# Mtx6BR_V2.net
KiCad netlist of a schematic drawn in EAGLE
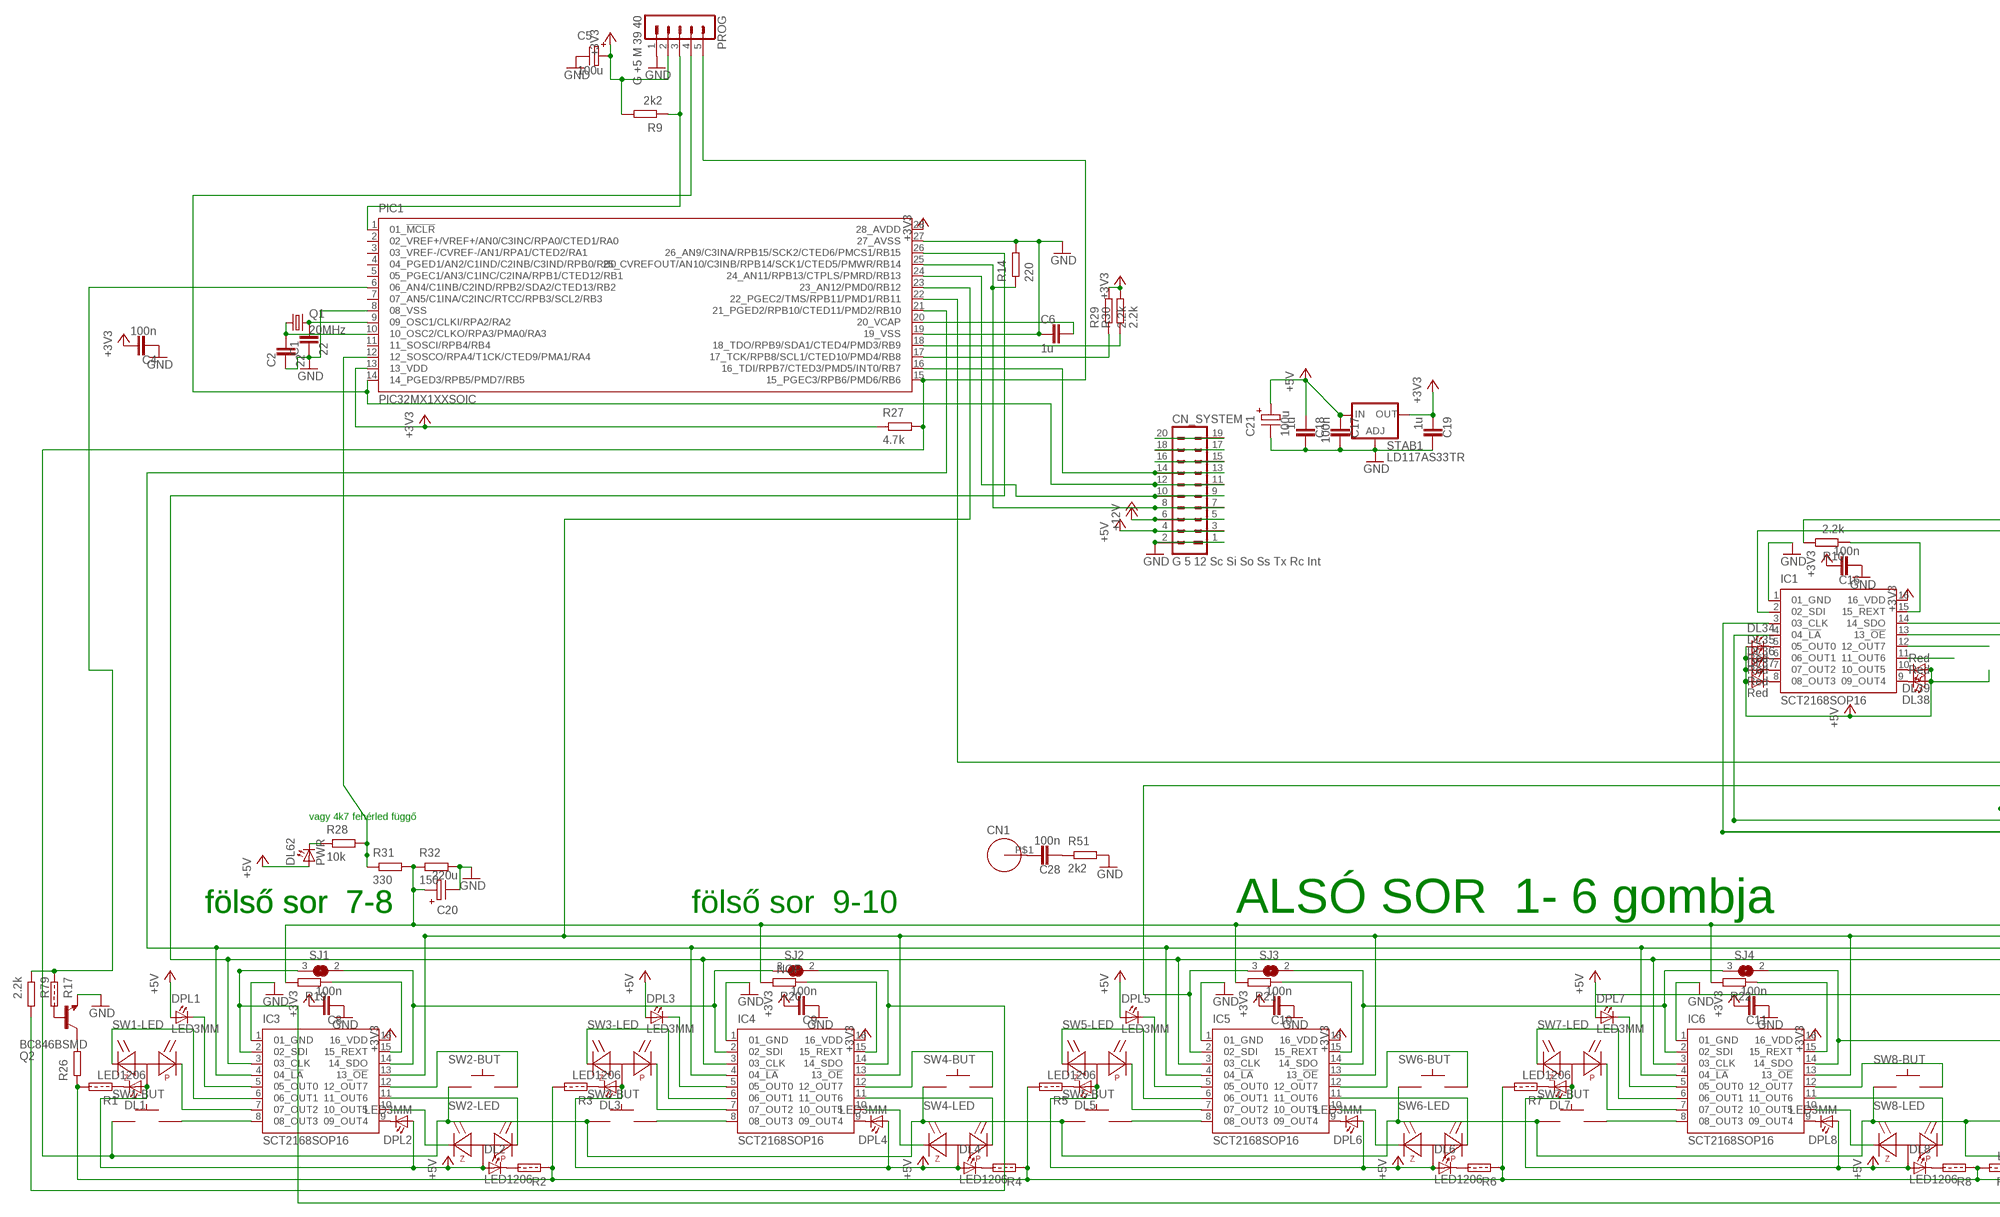
[diagram p0: schematic, sheet 1, part 1 of 2]
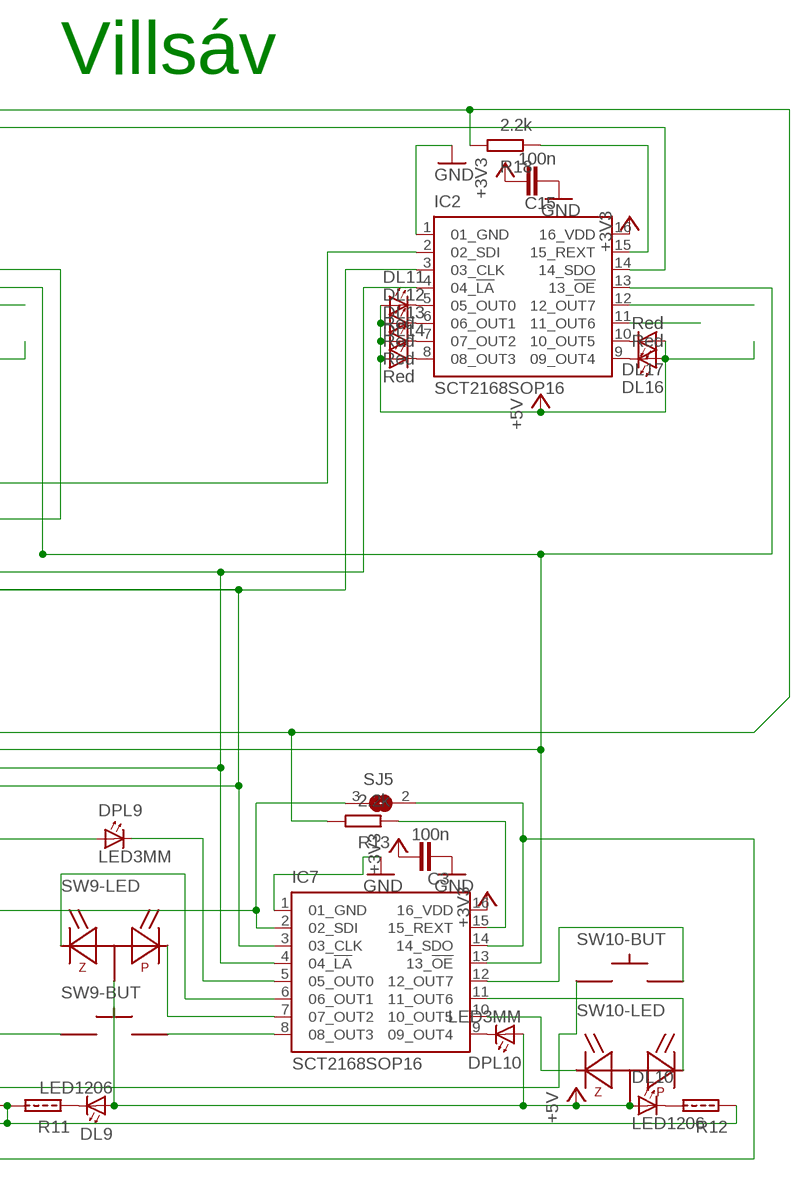
[diagram p1: schematic, sheet 1, part 2 of 2]

(export (version "E")
  (design (tool "Eeschema 10.0.6"))
  (components
    (comp (ref "C1")
      (value "22")
      (footprint "eagle-import:R0805")
      (libsource (lib "eagle-import") (part "C0805"))
    )
    (comp (ref "C2")
      (value "22")
      (footprint "eagle-import:R0805")
      (libsource (lib "eagle-import") (part "C0805"))
    )
    (comp (ref "C3")
      (value "100n")
      (footprint "eagle-import:R0805")
      (libsource (lib "eagle-import") (part "C0805"))
    )
    (comp (ref "C4")
      (value "100n")
      (footprint "eagle-import:R0805")
      (libsource (lib "eagle-import") (part "C0805"))
    )
    (comp (ref "C5")
      (value "100u")
      (footprint "eagle-import:C_EL1RASZT07")
      (libsource (lib "eagle-import") (part "C_EL1R07"))
    )
    (comp (ref "C6")
      (value "1u")
      (footprint "eagle-import:R0805")
      (libsource (lib "eagle-import") (part "C0805"))
    )
    (comp (ref "C8")
      (value "100n")
      (footprint "eagle-import:R0805")
      (libsource (lib "eagle-import") (part "C0805"))
    )
    (comp (ref "C9")
      (value "100n")
      (footprint "eagle-import:R0805")
      (libsource (lib "eagle-import") (part "C0805"))
    )
    (comp (ref "C10")
      (value "100n")
      (footprint "eagle-import:R0805")
      (libsource (lib "eagle-import") (part "C0805"))
    )
    (comp (ref "C11")
      (value "100n")
      (footprint "eagle-import:R0805")
      (libsource (lib "eagle-import") (part "C0805"))
    )
    (comp (ref "C15")
      (value "100n")
      (footprint "eagle-import:R0805")
      (libsource (lib "eagle-import") (part "C0805"))
    )
    (comp (ref "C16")
      (value "100n")
      (footprint "eagle-import:R0805")
      (libsource (lib "eagle-import") (part "C0805"))
    )
    (comp (ref "C17")
      (value "100n")
      (footprint "eagle-import:R0805")
      (libsource (lib "eagle-import") (part "C0805"))
    )
    (comp (ref "C18")
      (value "1u")
      (footprint "eagle-import:R0805")
      (libsource (lib "eagle-import") (part "C0805"))
    )
    (comp (ref "C19")
      (value "1u")
      (footprint "eagle-import:R0805")
      (libsource (lib "eagle-import") (part "C0805"))
    )
    (comp (ref "C20")
      (value "220u")
      (footprint "eagle-import:C_EL1RASZT07")
      (libsource (lib "eagle-import") (part "C_EL1R07"))
    )
    (comp (ref "C21")
      (value "100u")
      (footprint "eagle-import:C_EL1RASZT07")
      (libsource (lib "eagle-import") (part "C_EL1R07"))
    )
    (comp (ref "C28")
      (value "100n")
      (footprint "eagle-import:R0805")
      (libsource (lib "eagle-import") (part "C0805"))
    )
    (comp (ref "CN1")
      (value "TESTCSAVAR3.5")
      (footprint "eagle-import:TESTCSAVAR_3.5")
      (libsource (lib "eagle-import") (part "TESTCSAVAR3.5"))
    )
    (comp (ref "CN_SYSTEM")
      (value "G 5 12 Sc Si So Ss Tx Rc Int")
      (footprint "eagle-import:PIN10_2")
      (libsource (lib "eagle-import") (part "PIN10_2"))
    )
    (comp (ref "DL1")
      (value "LED1206")
      (footprint "eagle-import:R1206")
      (libsource (lib "eagle-import") (part "LED1206"))
    )
    (comp (ref "DL2")
      (value "LED1206")
      (footprint "eagle-import:R1206")
      (libsource (lib "eagle-import") (part "LED1206"))
    )
    (comp (ref "DL3")
      (value "LED1206")
      (footprint "eagle-import:R1206")
      (libsource (lib "eagle-import") (part "LED1206"))
    )
    (comp (ref "DL4")
      (value "LED1206")
      (footprint "eagle-import:R1206")
      (libsource (lib "eagle-import") (part "LED1206"))
    )
    (comp (ref "DL5")
      (value "LED1206")
      (footprint "eagle-import:R1206")
      (libsource (lib "eagle-import") (part "LED1206"))
    )
    (comp (ref "DL6")
      (value "LED1206")
      (footprint "eagle-import:R1206")
      (libsource (lib "eagle-import") (part "LED1206"))
    )
    (comp (ref "DL7")
      (value "LED1206")
      (footprint "eagle-import:R1206")
      (libsource (lib "eagle-import") (part "LED1206"))
    )
    (comp (ref "DL8")
      (value "LED1206")
      (footprint "eagle-import:R1206")
      (libsource (lib "eagle-import") (part "LED1206"))
    )
    (comp (ref "DL9")
      (value "LED1206")
      (footprint "eagle-import:R1206")
      (libsource (lib "eagle-import") (part "LED1206"))
    )
    (comp (ref "DL10")
      (value "LED1206")
      (footprint "eagle-import:R1206")
      (libsource (lib "eagle-import") (part "LED1206"))
    )
    (comp (ref "DL11")
      (value "Red")
      (footprint "eagle-import:LED5MM")
      (libsource (lib "eagle-import") (part "LED5MM"))
    )
    (comp (ref "DL12")
      (value "Red")
      (footprint "eagle-import:LED5MM")
      (libsource (lib "eagle-import") (part "LED5MM"))
    )
    (comp (ref "DL13")
      (value "Red")
      (footprint "eagle-import:LED5MM")
      (libsource (lib "eagle-import") (part "LED5MM"))
    )
    (comp (ref "DL14")
      (value "Red")
      (footprint "eagle-import:LED5MM")
      (libsource (lib "eagle-import") (part "LED5MM"))
    )
    (comp (ref "DL16")
      (value "Red")
      (footprint "eagle-import:LED5MM")
      (libsource (lib "eagle-import") (part "LED5MM"))
    )
    (comp (ref "DL17")
      (value "Red")
      (footprint "eagle-import:LED5MM")
      (libsource (lib "eagle-import") (part "LED5MM"))
    )
    (comp (ref "DL34")
      (value "Red")
      (footprint "eagle-import:LED5MM")
      (libsource (lib "eagle-import") (part "LED5MM"))
    )
    (comp (ref "DL35")
      (value "Red")
      (footprint "eagle-import:LED5MM")
      (libsource (lib "eagle-import") (part "LED5MM"))
    )
    (comp (ref "DL36")
      (value "Red")
      (footprint "eagle-import:LED5MM")
      (libsource (lib "eagle-import") (part "LED5MM"))
    )
    (comp (ref "DL37")
      (value "Red")
      (footprint "eagle-import:LED5MM")
      (libsource (lib "eagle-import") (part "LED5MM"))
    )
    (comp (ref "DL38")
      (value "Red")
      (footprint "eagle-import:LED5MM")
      (libsource (lib "eagle-import") (part "LED5MM"))
    )
    (comp (ref "DL39")
      (value "Red")
      (footprint "eagle-import:LED5MM")
      (libsource (lib "eagle-import") (part "LED5MM"))
    )
    (comp (ref "DL62")
      (value "PWR")
      (footprint "eagle-import:LED5MM")
      (libsource (lib "eagle-import") (part "LED5MM"))
    )
    (comp (ref "DPL1")
      (value "LED3MM")
      (footprint "eagle-import:LED3MM")
      (libsource (lib "eagle-import") (part "LED3MM"))
    )
    (comp (ref "DPL2")
      (value "LED3MM")
      (footprint "eagle-import:LED3MM")
      (libsource (lib "eagle-import") (part "LED3MM"))
    )
    (comp (ref "DPL3")
      (value "LED3MM")
      (footprint "eagle-import:LED3MM")
      (libsource (lib "eagle-import") (part "LED3MM"))
    )
    (comp (ref "DPL4")
      (value "LED3MM")
      (footprint "eagle-import:LED3MM")
      (libsource (lib "eagle-import") (part "LED3MM"))
    )
    (comp (ref "DPL5")
      (value "LED3MM")
      (footprint "eagle-import:LED3MM")
      (libsource (lib "eagle-import") (part "LED3MM"))
    )
    (comp (ref "DPL6")
      (value "LED3MM")
      (footprint "eagle-import:LED3MM")
      (libsource (lib "eagle-import") (part "LED3MM"))
    )
    (comp (ref "DPL7")
      (value "LED3MM")
      (footprint "eagle-import:LED3MM")
      (libsource (lib "eagle-import") (part "LED3MM"))
    )
    (comp (ref "DPL8")
      (value "LED3MM")
      (footprint "eagle-import:LED3MM")
      (libsource (lib "eagle-import") (part "LED3MM"))
    )
    (comp (ref "DPL9")
      (value "LED3MM")
      (footprint "eagle-import:LED3MM")
      (libsource (lib "eagle-import") (part "LED3MM"))
    )
    (comp (ref "DPL10")
      (value "LED3MM")
      (footprint "eagle-import:LED3MM")
      (libsource (lib "eagle-import") (part "LED3MM"))
    )
    (comp (ref "IC1")
      (value "SCT2168SOP16")
      (footprint "eagle-import:SO16")
      (libsource (lib "eagle-import") (part "SCT2168SOP16"))
    )
    (comp (ref "IC2")
      (value "SCT2168SOP16")
      (footprint "eagle-import:SO16")
      (libsource (lib "eagle-import") (part "SCT2168SOP16"))
    )
    (comp (ref "IC3")
      (value "SCT2168SOP16")
      (footprint "eagle-import:SO16")
      (libsource (lib "eagle-import") (part "SCT2168SOP16"))
    )
    (comp (ref "IC4")
      (value "SCT2168SOP16")
      (footprint "eagle-import:SO16")
      (libsource (lib "eagle-import") (part "SCT2168SOP16"))
    )
    (comp (ref "IC5")
      (value "SCT2168SOP16")
      (footprint "eagle-import:SO16")
      (libsource (lib "eagle-import") (part "SCT2168SOP16"))
    )
    (comp (ref "IC6")
      (value "SCT2168SOP16")
      (footprint "eagle-import:SO16")
      (libsource (lib "eagle-import") (part "SCT2168SOP16"))
    )
    (comp (ref "IC7")
      (value "SCT2168SOP16")
      (footprint "eagle-import:SO16")
      (libsource (lib "eagle-import") (part "SCT2168SOP16"))
    )
    (comp (ref "PIC1")
      (value "PIC32MX1XXSOIC")
      (footprint "eagle-import:SOIC127P1032X265-28N")
      (libsource (lib "eagle-import") (part "PIC32MX1XXSOIC"))
    )
    (comp (ref "PROG")
      (value "G +5 M 39 40")
      (footprint "eagle-import:PIN05_1")
      (libsource (lib "eagle-import") (part "PIN05_1"))
    )
    (comp (ref "Q1")
      (value "20MHz")
      (footprint "eagle-import:XTAL_NAGYSMD")
      (libsource (lib "eagle-import") (part "XTAL_2NAGYSMD"))
    )
    (comp (ref "Q2")
      (value "BC846BSMD")
      (footprint "eagle-import:SOT23")
      (libsource (lib "eagle-import") (part "BC846SMDB"))
    )
    (comp (ref "R1")
      (value "RNULL_EU0805")
      (footprint "eagle-import:R0805_C")
      (libsource (lib "eagle-import") (part "RNULL_EU0805"))
    )
    (comp (ref "R2")
      (value "RNULL_EU0805")
      (footprint "eagle-import:R0805_C")
      (libsource (lib "eagle-import") (part "RNULL_EU0805"))
    )
    (comp (ref "R3")
      (value "RNULL_EU0805")
      (footprint "eagle-import:R0805_C")
      (libsource (lib "eagle-import") (part "RNULL_EU0805"))
    )
    (comp (ref "R4")
      (value "RNULL_EU0805")
      (footprint "eagle-import:R0805_C")
      (libsource (lib "eagle-import") (part "RNULL_EU0805"))
    )
    (comp (ref "R5")
      (value "RNULL_EU0805")
      (footprint "eagle-import:R0805_C")
      (libsource (lib "eagle-import") (part "RNULL_EU0805"))
    )
    (comp (ref "R6")
      (value "RNULL_EU0805")
      (footprint "eagle-import:R0805_C")
      (libsource (lib "eagle-import") (part "RNULL_EU0805"))
    )
    (comp (ref "R7")
      (value "RNULL_EU0805")
      (footprint "eagle-import:R0805_C")
      (libsource (lib "eagle-import") (part "RNULL_EU0805"))
    )
    (comp (ref "R8")
      (value "RNULL_EU0805")
      (footprint "eagle-import:R0805_C")
      (libsource (lib "eagle-import") (part "RNULL_EU0805"))
    )
    (comp (ref "R9")
      (value "2k2")
      (footprint "eagle-import:R0805")
      (libsource (lib "eagle-import") (part "R_EU0805"))
    )
    (comp (ref "R10")
      (value "2.2k")
      (footprint "eagle-import:R0805")
      (libsource (lib "eagle-import") (part "R_EU0805"))
    )
    (comp (ref "R11")
      (value "RNULL_EU0805")
      (footprint "eagle-import:R0805_C")
      (libsource (lib "eagle-import") (part "RNULL_EU0805"))
    )
    (comp (ref "R12")
      (value "RNULL_EU0805")
      (footprint "eagle-import:R0805_C")
      (libsource (lib "eagle-import") (part "RNULL_EU0805"))
    )
    (comp (ref "R13")
      (value "2.2k")
      (footprint "eagle-import:R0805")
      (libsource (lib "eagle-import") (part "R_EU0805"))
    )
    (comp (ref "R14")
      (value "220")
      (footprint "eagle-import:R0805")
      (libsource (lib "eagle-import") (part "R_EU0805"))
    )
    (comp (ref "R17")
      (value "RNULL_EU0805")
      (footprint "eagle-import:R0805_C")
      (libsource (lib "eagle-import") (part "RNULL_EU0805"))
    )
    (comp (ref "R18")
      (value "2.2k")
      (footprint "eagle-import:R0805")
      (libsource (lib "eagle-import") (part "R_EU0805"))
    )
    (comp (ref "R19")
      (value "R_EU0805")
      (footprint "eagle-import:R0805")
      (libsource (lib "eagle-import") (part "R_EU0805"))
    )
    (comp (ref "R20")
      (value "NOP")
      (footprint "eagle-import:R0805")
      (libsource (lib "eagle-import") (part "R_EU0805"))
    )
    (comp (ref "R21")
      (value "R_EU0805")
      (footprint "eagle-import:R0805")
      (libsource (lib "eagle-import") (part "R_EU0805"))
    )
    (comp (ref "R22")
      (value "R_EU0805")
      (footprint "eagle-import:R0805")
      (libsource (lib "eagle-import") (part "R_EU0805"))
    )
    (comp (ref "R26")
      (value "R_EU0805")
      (footprint "eagle-import:R0805")
      (libsource (lib "eagle-import") (part "R_EU0805"))
    )
    (comp (ref "R27")
      (value "4.7k")
      (footprint "eagle-import:R0805")
      (libsource (lib "eagle-import") (part "R_EU0805"))
    )
    (comp (ref "R28")
      (value "10k")
      (footprint "eagle-import:R0805")
      (libsource (lib "eagle-import") (part "R_EU0805"))
    )
    (comp (ref "R29")
      (value "2.2k")
      (footprint "eagle-import:R0805")
      (libsource (lib "eagle-import") (part "R_EU0805"))
    )
    (comp (ref "R30")
      (value "2.2k")
      (footprint "eagle-import:R0805")
      (libsource (lib "eagle-import") (part "R_EU0805"))
    )
    (comp (ref "R31")
      (value "330")
      (footprint "eagle-import:R0805")
      (libsource (lib "eagle-import") (part "R_EU0805"))
    )
    (comp (ref "R32")
      (value "150")
      (footprint "eagle-import:R0805")
      (libsource (lib "eagle-import") (part "R_EU0805"))
    )
    (comp (ref "R51")
      (value "2k2")
      (footprint "eagle-import:R0805")
      (libsource (lib "eagle-import") (part "R_EU0805"))
    )
    (comp (ref "R79")
      (value "2.2k")
      (footprint "eagle-import:R0805")
      (libsource (lib "eagle-import") (part "R_EU0805"))
    )
    (comp (ref "SJ1") (value "SJ") (footprint "eagle-import:SJ") (libsource (lib "eagle-import") (part "SJ")))
    (comp (ref "SJ2") (value "SJ") (footprint "eagle-import:SJ") (libsource (lib "eagle-import") (part "SJ")))
    (comp (ref "SJ3") (value "SJ") (footprint "eagle-import:SJ") (libsource (lib "eagle-import") (part "SJ")))
    (comp (ref "SJ4") (value "SJ") (footprint "eagle-import:SJ") (libsource (lib "eagle-import") (part "SJ")))
    (comp (ref "SJ5") (value "SJ") (footprint "eagle-import:SJ") (libsource (lib "eagle-import") (part "SJ")))
    (comp (ref "STAB1")
      (value "LD117AS33TR")
      (footprint "eagle-import:SOT223")
      (libsource (lib "eagle-import") (part "LD117A?S33TR"))
    )
    (comp (ref "SW1")
      (value "SPG2")
      (footprint "eagle-import:SPG2_3LED")
      (libsource (lib "eagle-import") (part "SPG2"))
    )
    (comp (ref "SW2")
      (value "SPG2")
      (footprint "eagle-import:SPG2_3LED")
      (libsource (lib "eagle-import") (part "SPG2"))
    )
    (comp (ref "SW3")
      (value "SPG2")
      (footprint "eagle-import:SPG2_3LED")
      (libsource (lib "eagle-import") (part "SPG2"))
    )
    (comp (ref "SW4")
      (value "SPG2")
      (footprint "eagle-import:SPG2_3LED")
      (libsource (lib "eagle-import") (part "SPG2"))
    )
    (comp (ref "SW5")
      (value "SPG2")
      (footprint "eagle-import:SPG2_3LED")
      (libsource (lib "eagle-import") (part "SPG2"))
    )
    (comp (ref "SW6")
      (value "SPG2")
      (footprint "eagle-import:SPG2_3LED")
      (libsource (lib "eagle-import") (part "SPG2"))
    )
    (comp (ref "SW7")
      (value "SPG2")
      (footprint "eagle-import:SPG2_3LED")
      (libsource (lib "eagle-import") (part "SPG2"))
    )
    (comp (ref "SW8")
      (value "SPG2")
      (footprint "eagle-import:SPG2_3LED")
      (libsource (lib "eagle-import") (part "SPG2"))
    )
    (comp (ref "SW9")
      (value "SPG2")
      (footprint "eagle-import:SPG2_3LED")
      (libsource (lib "eagle-import") (part "SPG2"))
    )
    (comp (ref "SW10")
      (value "SPG2")
      (footprint "eagle-import:SPG2_3LED")
      (libsource (lib "eagle-import") (part "SPG2"))
    )
  )
  (nets
    (net (code "1") (name "+3V3") (class "Default")
      (node (ref "C10") (pin "1") (pinfunction "1_1") (pintype "passive"))
      (node (ref "C11") (pin "1") (pinfunction "1_1") (pintype "passive"))
      (node (ref "C15") (pin "1") (pinfunction "1_1") (pintype "passive"))
      (node (ref "C16") (pin "1") (pinfunction "1_1") (pintype "passive"))
      (node (ref "C19") (pin "2") (pinfunction "2_2") (pintype "passive"))
      (node (ref "C3") (pin "1") (pinfunction "1_1") (pintype "passive"))
      (node (ref "C4") (pin "1") (pinfunction "1_1") (pintype "passive"))
      (node (ref "C5") (pin "P+") (pinfunction "P+_P+") (pintype "passive"))
      (node (ref "C8") (pin "1") (pinfunction "1_1") (pintype "passive"))
      (node (ref "C9") (pin "1") (pinfunction "1_1") (pintype "passive"))
      (node (ref "IC1") (pin "16") (pinfunction "16_VDD_16") (pintype "power_in"))
      (node (ref "IC2") (pin "16") (pinfunction "16_VDD_16") (pintype "power_in"))
      (node (ref "IC3") (pin "16") (pinfunction "16_VDD_16") (pintype "power_in"))
      (node (ref "IC4") (pin "16") (pinfunction "16_VDD_16") (pintype "power_in"))
      (node (ref "IC5") (pin "16") (pinfunction "16_VDD_16") (pintype "power_in"))
      (node (ref "IC6") (pin "16") (pinfunction "16_VDD_16") (pintype "power_in"))
      (node (ref "IC7") (pin "16") (pinfunction "16_VDD_16") (pintype "power_in"))
      (node (ref "PIC1") (pin "13") (pinfunction "13_VDD_13") (pintype "bidirectional"))
      (node (ref "PIC1") (pin "28") (pinfunction "28_AVDD_28") (pintype "bidirectional"))
      (node (ref "PROG") (pin "2") (pinfunction "2_2") (pintype "passive"))
      (node (ref "R27") (pin "1") (pinfunction "A_1") (pintype "passive"))
      (node (ref "R29") (pin "2") (pinfunction "E_2") (pintype "passive"))
      (node (ref "R30") (pin "2") (pinfunction "E_2") (pintype "passive"))
      (node (ref "R9") (pin "2") (pinfunction "E_2") (pintype "passive"))
      (node (ref "STAB1") (pin "4") (pinfunction "OUT_4") (pintype "passive"))
    )
    (net (code "2") (name "+5V") (class "Default")
      (node (ref "C17") (pin "2") (pinfunction "2_2") (pintype "passive"))
      (node (ref "C18") (pin "2") (pinfunction "2_2") (pintype "passive"))
      (node (ref "C21") (pin "P+") (pinfunction "P+_P+") (pintype "passive"))
      (node (ref "CN_SYSTEM") (pin "3") (pinfunction "3_3") (pintype "passive"))
      (node (ref "CN_SYSTEM") (pin "4") (pinfunction "4_4") (pintype "passive"))
      (node (ref "DL1") (pin "1") (pinfunction "A_1") (pintype "passive"))
      (node (ref "DL10") (pin "1") (pinfunction "A_1") (pintype "passive"))
      (node (ref "DL11") (pin "A") (pinfunction "A_A") (pintype "passive"))
      (node (ref "DL12") (pin "A") (pinfunction "A_A") (pintype "passive"))
      (node (ref "DL13") (pin "A") (pinfunction "A_A") (pintype "passive"))
      (node (ref "DL14") (pin "A") (pinfunction "A_A") (pintype "passive"))
      (node (ref "DL16") (pin "A") (pinfunction "A_A") (pintype "passive"))
      (node (ref "DL17") (pin "A") (pinfunction "A_A") (pintype "passive"))
      (node (ref "DL2") (pin "1") (pinfunction "A_1") (pintype "passive"))
      (node (ref "DL3") (pin "1") (pinfunction "A_1") (pintype "passive"))
      (node (ref "DL34") (pin "A") (pinfunction "A_A") (pintype "passive"))
      (node (ref "DL35") (pin "A") (pinfunction "A_A") (pintype "passive"))
      (node (ref "DL36") (pin "A") (pinfunction "A_A") (pintype "passive"))
      (node (ref "DL37") (pin "A") (pinfunction "A_A") (pintype "passive"))
      (node (ref "DL38") (pin "A") (pinfunction "A_A") (pintype "passive"))
      (node (ref "DL39") (pin "A") (pinfunction "A_A") (pintype "passive"))
      (node (ref "DL4") (pin "1") (pinfunction "A_1") (pintype "passive"))
      (node (ref "DL5") (pin "1") (pinfunction "A_1") (pintype "passive"))
      (node (ref "DL6") (pin "1") (pinfunction "A_1") (pintype "passive"))
      (node (ref "DL62") (pin "A") (pinfunction "A_A") (pintype "passive"))
      (node (ref "DL7") (pin "1") (pinfunction "A_1") (pintype "passive"))
      (node (ref "DL8") (pin "1") (pinfunction "A_1") (pintype "passive"))
      (node (ref "DL9") (pin "1") (pinfunction "A_1") (pintype "passive"))
      (node (ref "DPL1") (pin "A") (pinfunction "A_A") (pintype "passive"))
      (node (ref "DPL10") (pin "A") (pinfunction "A_A") (pintype "passive"))
      (node (ref "DPL2") (pin "A") (pinfunction "A_A") (pintype "passive"))
      (node (ref "DPL3") (pin "A") (pinfunction "A_A") (pintype "passive"))
      (node (ref "DPL4") (pin "A") (pinfunction "A_A") (pintype "passive"))
      (node (ref "DPL5") (pin "A") (pinfunction "A_A") (pintype "passive"))
      (node (ref "DPL6") (pin "A") (pinfunction "A_A") (pintype "passive"))
      (node (ref "DPL7") (pin "A") (pinfunction "A_A") (pintype "passive"))
      (node (ref "DPL8") (pin "A") (pinfunction "A_A") (pintype "passive"))
      (node (ref "DPL9") (pin "A") (pinfunction "A_A") (pintype "passive"))
      (node (ref "STAB1") (pin "3") (pinfunction "IN_3") (pintype "input"))
      (node (ref "SW1") (pin "LED+") (pinfunction "+_LED+") (pintype "bidirectional"))
      (node (ref "SW10") (pin "LED+") (pinfunction "+_LED+") (pintype "bidirectional"))
      (node (ref "SW2") (pin "LED+") (pinfunction "+_LED+") (pintype "bidirectional"))
      (node (ref "SW3") (pin "LED+") (pinfunction "+_LED+") (pintype "bidirectional"))
      (node (ref "SW4") (pin "LED+") (pinfunction "+_LED+") (pintype "bidirectional"))
      (node (ref "SW5") (pin "LED+") (pinfunction "+_LED+") (pintype "bidirectional"))
      (node (ref "SW6") (pin "LED+") (pinfunction "+_LED+") (pintype "bidirectional"))
      (node (ref "SW7") (pin "LED+") (pinfunction "+_LED+") (pintype "bidirectional"))
      (node (ref "SW8") (pin "LED+") (pinfunction "+_LED+") (pintype "bidirectional"))
      (node (ref "SW9") (pin "LED+") (pinfunction "+_LED+") (pintype "bidirectional"))
    )
    (net (code "3") (name "+12V") (class "Default")
      (node (ref "CN_SYSTEM") (pin "5") (pinfunction "5_5") (pintype "passive"))
      (node (ref "CN_SYSTEM") (pin "6") (pinfunction "6_6") (pintype "passive"))
    )
    (net (code "4") (name "GND") (class "Default")
      (node (ref "C1") (pin "2") (pinfunction "2_2") (pintype "passive"))
      (node (ref "C10") (pin "2") (pinfunction "2_2") (pintype "passive"))
      (node (ref "C11") (pin "2") (pinfunction "2_2") (pintype "passive"))
      (node (ref "C15") (pin "2") (pinfunction "2_2") (pintype "passive"))
      (node (ref "C16") (pin "2") (pinfunction "2_2") (pintype "passive"))
      (node (ref "C17") (pin "1") (pinfunction "1_1") (pintype "passive"))
      (node (ref "C18") (pin "1") (pinfunction "1_1") (pintype "passive"))
      (node (ref "C19") (pin "1") (pinfunction "1_1") (pintype "passive"))
      (node (ref "C2") (pin "2") (pinfunction "2_2") (pintype "passive"))
      (node (ref "C20") (pin "P-") (pinfunction "P-_P-") (pintype "passive"))
      (node (ref "C21") (pin "P-") (pinfunction "P-_P-") (pintype "passive"))
      (node (ref "C3") (pin "2") (pinfunction "2_2") (pintype "passive"))
      (node (ref "C4") (pin "2") (pinfunction "2_2") (pintype "passive"))
      (node (ref "C5") (pin "P-") (pinfunction "P-_P-") (pintype "passive"))
      (node (ref "C6") (pin "2") (pinfunction "2_2") (pintype "passive"))
      (node (ref "C8") (pin "2") (pinfunction "2_2") (pintype "passive"))
      (node (ref "C9") (pin "2") (pinfunction "2_2") (pintype "passive"))
      (node (ref "CN_SYSTEM") (pin "1") (pinfunction "1_1") (pintype "passive"))
      (node (ref "CN_SYSTEM") (pin "2") (pinfunction "2_2") (pintype "passive"))
      (node (ref "IC1") (pin "1") (pinfunction "01_GND_1") (pintype "power_in"))
      (node (ref "IC2") (pin "1") (pinfunction "01_GND_1") (pintype "power_in"))
      (node (ref "IC3") (pin "1") (pinfunction "01_GND_1") (pintype "power_in"))
      (node (ref "IC4") (pin "1") (pinfunction "01_GND_1") (pintype "power_in"))
      (node (ref "IC5") (pin "1") (pinfunction "01_GND_1") (pintype "power_in"))
      (node (ref "IC6") (pin "1") (pinfunction "01_GND_1") (pintype "power_in"))
      (node (ref "IC7") (pin "1") (pinfunction "01_GND_1") (pintype "power_in"))
      (node (ref "PIC1") (pin "19") (pinfunction "19_VSS_19") (pintype "power_in"))
      (node (ref "PIC1") (pin "27") (pinfunction "27_AVSS_27") (pintype "bidirectional"))
      (node (ref "PIC1") (pin "8") (pinfunction "08_VSS_8") (pintype "power_in"))
      (node (ref "PROG") (pin "1") (pinfunction "1_1") (pintype "passive"))
      (node (ref "Q2") (pin "2") (pinfunction "E_2") (pintype "passive"))
      (node (ref "R14") (pin "2") (pinfunction "E_2") (pintype "passive"))
      (node (ref "R32") (pin "2") (pinfunction "E_2") (pintype "passive"))
      (node (ref "R51") (pin "2") (pinfunction "E_2") (pintype "passive"))
      (node (ref "STAB1") (pin "1") (pinfunction "ADJ_1") (pintype "input"))
    )
    (net (code "5") (name "Net-(CN1-1)") (class "Default")
      (node (ref "C28") (pin "1") (pinfunction "1_1") (pintype "passive"))
      (node (ref "CN1") (pin "P$1") (pinfunction "1_P$1") (pintype "passive"))
    )
    (net (code "6") (name "Net-(CN_SYSTEM-Pad15)") (class "Default")
      (node (ref "CN_SYSTEM") (pin "15") (pinfunction "15_15") (pintype "passive"))
      (node (ref "CN_SYSTEM") (pin "16") (pinfunction "16_16") (pintype "passive"))
    )
    (net (code "7") (name "Net-(CN_SYSTEM-Pad17)") (class "Default")
      (node (ref "CN_SYSTEM") (pin "17") (pinfunction "17_17") (pintype "passive"))
      (node (ref "CN_SYSTEM") (pin "18") (pinfunction "18_18") (pintype "passive"))
    )
    (net (code "8") (name "Net-(CN_SYSTEM-Pad19)") (class "Default")
      (node (ref "CN_SYSTEM") (pin "19") (pinfunction "19_19") (pintype "passive"))
      (node (ref "CN_SYSTEM") (pin "20") (pinfunction "20_20") (pintype "passive"))
    )
    (net (code "9") (name "Net-(DL1-C)") (class "Default")
      (node (ref "DL1") (pin "2") (pinfunction "C_2") (pintype "passive"))
      (node (ref "R1") (pin "1") (pinfunction "A_1") (pintype "passive"))
    )
    (net (code "10") (name "Net-(DL2-C)") (class "Default")
      (node (ref "DL2") (pin "2") (pinfunction "C_2") (pintype "passive"))
      (node (ref "R2") (pin "2") (pinfunction "E_2") (pintype "passive"))
    )
    (net (code "11") (name "Net-(DL3-C)") (class "Default")
      (node (ref "DL3") (pin "2") (pinfunction "C_2") (pintype "passive"))
      (node (ref "R3") (pin "1") (pinfunction "A_1") (pintype "passive"))
    )
    (net (code "12") (name "Net-(DL4-C)") (class "Default")
      (node (ref "DL4") (pin "2") (pinfunction "C_2") (pintype "passive"))
      (node (ref "R4") (pin "2") (pinfunction "E_2") (pintype "passive"))
    )
    (net (code "13") (name "Net-(DL5-C)") (class "Default")
      (node (ref "DL5") (pin "2") (pinfunction "C_2") (pintype "passive"))
      (node (ref "R5") (pin "1") (pinfunction "A_1") (pintype "passive"))
    )
    (net (code "14") (name "Net-(DL6-C)") (class "Default")
      (node (ref "DL6") (pin "2") (pinfunction "C_2") (pintype "passive"))
      (node (ref "R6") (pin "2") (pinfunction "E_2") (pintype "passive"))
    )
    (net (code "15") (name "Net-(DL7-C)") (class "Default")
      (node (ref "DL7") (pin "2") (pinfunction "C_2") (pintype "passive"))
      (node (ref "R7") (pin "1") (pinfunction "A_1") (pintype "passive"))
    )
    (net (code "16") (name "Net-(DL8-C)") (class "Default")
      (node (ref "DL8") (pin "2") (pinfunction "C_2") (pintype "passive"))
      (node (ref "R8") (pin "2") (pinfunction "E_2") (pintype "passive"))
    )
    (net (code "17") (name "Net-(DL9-C)") (class "Default")
      (node (ref "DL9") (pin "2") (pinfunction "C_2") (pintype "passive"))
      (node (ref "R11") (pin "1") (pinfunction "A_1") (pintype "passive"))
    )
    (net (code "18") (name "Net-(DL10-C)") (class "Default")
      (node (ref "DL10") (pin "2") (pinfunction "C_2") (pintype "passive"))
      (node (ref "R12") (pin "2") (pinfunction "E_2") (pintype "passive"))
    )
    (net (code "19") (name "Net-(DL11-C)") (class "Default")
      (node (ref "DL11") (pin "K") (pinfunction "C_K") (pintype "passive"))
      (node (ref "IC2") (pin "5") (pinfunction "05_OUT0_5") (pintype "output"))
    )
    (net (code "20") (name "Net-(DL12-C)") (class "Default")
      (node (ref "DL12") (pin "K") (pinfunction "C_K") (pintype "passive"))
      (node (ref "IC2") (pin "6") (pinfunction "06_OUT1_6") (pintype "output"))
    )
    (net (code "21") (name "Net-(DL13-C)") (class "Default")
      (node (ref "DL13") (pin "K") (pinfunction "C_K") (pintype "passive"))
      (node (ref "IC2") (pin "7") (pinfunction "07_OUT2_7") (pintype "output"))
    )
    (net (code "22") (name "Net-(DL14-C)") (class "Default")
      (node (ref "DL14") (pin "K") (pinfunction "C_K") (pintype "passive"))
      (node (ref "IC2") (pin "8") (pinfunction "08_OUT3_8") (pintype "output"))
    )
    (net (code "23") (name "Net-(DL16-C)") (class "Default")
      (node (ref "DL16") (pin "K") (pinfunction "C_K") (pintype "passive"))
      (node (ref "IC2") (pin "9") (pinfunction "09_OUT4_9") (pintype "output"))
    )
    (net (code "24") (name "Net-(DL17-C)") (class "Default")
      (node (ref "DL17") (pin "K") (pinfunction "C_K") (pintype "passive"))
      (node (ref "IC2") (pin "10") (pinfunction "10_OUT5_10") (pintype "output"))
    )
    (net (code "25") (name "Net-(DL34-C)") (class "Default")
      (node (ref "DL34") (pin "K") (pinfunction "C_K") (pintype "passive"))
      (node (ref "IC1") (pin "5") (pinfunction "05_OUT0_5") (pintype "output"))
    )
    (net (code "26") (name "Net-(DL35-C)") (class "Default")
      (node (ref "DL35") (pin "K") (pinfunction "C_K") (pintype "passive"))
      (node (ref "IC1") (pin "6") (pinfunction "06_OUT1_6") (pintype "output"))
    )
    (net (code "27") (name "Net-(DL36-C)") (class "Default")
      (node (ref "DL36") (pin "K") (pinfunction "C_K") (pintype "passive"))
      (node (ref "IC1") (pin "7") (pinfunction "07_OUT2_7") (pintype "output"))
    )
    (net (code "28") (name "Net-(DL37-C)") (class "Default")
      (node (ref "DL37") (pin "K") (pinfunction "C_K") (pintype "passive"))
      (node (ref "IC1") (pin "8") (pinfunction "08_OUT3_8") (pintype "output"))
    )
    (net (code "29") (name "Net-(DL38-C)") (class "Default")
      (node (ref "DL38") (pin "K") (pinfunction "C_K") (pintype "passive"))
      (node (ref "IC1") (pin "9") (pinfunction "09_OUT4_9") (pintype "output"))
    )
    (net (code "30") (name "Net-(DL39-C)") (class "Default")
      (node (ref "DL39") (pin "K") (pinfunction "C_K") (pintype "passive"))
      (node (ref "IC1") (pin "10") (pinfunction "10_OUT5_10") (pintype "output"))
    )
    (net (code "31") (name "Net-(DL62-C)") (class "Default")
      (node (ref "DL62") (pin "K") (pinfunction "C_K") (pintype "passive"))
      (node (ref "R28") (pin "1") (pinfunction "A_1") (pintype "passive"))
    )
    (net (code "32") (name "Net-(DPL1-C)") (class "Default")
      (node (ref "DPL1") (pin "K") (pinfunction "C_K") (pintype "passive"))
      (node (ref "IC3") (pin "5") (pinfunction "05_OUT0_5") (pintype "output"))
    )
    (net (code "33") (name "Net-(DPL2-C)") (class "Default")
      (node (ref "DPL2") (pin "K") (pinfunction "C_K") (pintype "passive"))
      (node (ref "IC3") (pin "9") (pinfunction "09_OUT4_9") (pintype "output"))
    )
    (net (code "34") (name "Net-(DPL3-C)") (class "Default")
      (node (ref "DPL3") (pin "K") (pinfunction "C_K") (pintype "passive"))
      (node (ref "IC4") (pin "5") (pinfunction "05_OUT0_5") (pintype "output"))
    )
    (net (code "35") (name "Net-(DPL4-C)") (class "Default")
      (node (ref "DPL4") (pin "K") (pinfunction "C_K") (pintype "passive"))
      (node (ref "IC4") (pin "9") (pinfunction "09_OUT4_9") (pintype "output"))
    )
    (net (code "36") (name "Net-(DPL5-C)") (class "Default")
      (node (ref "DPL5") (pin "K") (pinfunction "C_K") (pintype "passive"))
      (node (ref "IC5") (pin "5") (pinfunction "05_OUT0_5") (pintype "output"))
    )
    (net (code "37") (name "Net-(DPL6-C)") (class "Default")
      (node (ref "DPL6") (pin "K") (pinfunction "C_K") (pintype "passive"))
      (node (ref "IC5") (pin "9") (pinfunction "09_OUT4_9") (pintype "output"))
    )
    (net (code "38") (name "Net-(DPL7-C)") (class "Default")
      (node (ref "DPL7") (pin "K") (pinfunction "C_K") (pintype "passive"))
      (node (ref "IC6") (pin "5") (pinfunction "05_OUT0_5") (pintype "output"))
    )
    (net (code "39") (name "Net-(DPL8-C)") (class "Default")
      (node (ref "DPL8") (pin "K") (pinfunction "C_K") (pintype "passive"))
      (node (ref "IC6") (pin "9") (pinfunction "09_OUT4_9") (pintype "output"))
    )
    (net (code "40") (name "Net-(DPL9-C)") (class "Default")
      (node (ref "DPL9") (pin "K") (pinfunction "C_K") (pintype "passive"))
      (node (ref "IC7") (pin "5") (pinfunction "05_OUT0_5") (pintype "output"))
    )
    (net (code "41") (name "Net-(DPL10-C)") (class "Default")
      (node (ref "DPL10") (pin "K") (pinfunction "C_K") (pintype "passive"))
      (node (ref "IC7") (pin "9") (pinfunction "09_OUT4_9") (pintype "output"))
    )
    (net (code "42") (name "Net-(IC1-02_SDI)") (class "Default")
      (node (ref "IC1") (pin "2") (pinfunction "02_SDI_2") (pintype "input"))
      (node (ref "IC2") (pin "14") (pinfunction "14_SDO_14") (pintype "output"))
    )
    (net (code "43") (name "Net-(IC1-03_CLK)") (class "Default")
      (node (ref "IC1") (pin "3") (pinfunction "03_CLK_3") (pintype "input"))
      (node (ref "IC2") (pin "3") (pinfunction "03_CLK_3") (pintype "input"))
      (node (ref "IC3") (pin "3") (pinfunction "03_CLK_3") (pintype "input"))
      (node (ref "IC4") (pin "3") (pinfunction "03_CLK_3") (pintype "input"))
      (node (ref "IC5") (pin "3") (pinfunction "03_CLK_3") (pintype "input"))
      (node (ref "IC6") (pin "3") (pinfunction "03_CLK_3") (pintype "input"))
      (node (ref "IC7") (pin "3") (pinfunction "03_CLK_3") (pintype "input"))
      (node (ref "PIC1") (pin "26") (pinfunction "26_AN9/C3INA/RPB15/SCK2/CTED6/PMCS1/RB15_26") (pintype "bidirectional"))
    )
    (net (code "44") (name "Net-(IC1-04_~{LA})") (class "Default")
      (node (ref "IC1") (pin "4") (pinfunction "04_~{LA}_4") (pintype "input"))
      (node (ref "IC2") (pin "4") (pinfunction "04_~{LA}_4") (pintype "input"))
      (node (ref "IC3") (pin "4") (pinfunction "04_~{LA}_4") (pintype "input"))
      (node (ref "IC4") (pin "4") (pinfunction "04_~{LA}_4") (pintype "input"))
      (node (ref "IC5") (pin "4") (pinfunction "04_~{LA}_4") (pintype "input"))
      (node (ref "IC6") (pin "4") (pinfunction "04_~{LA}_4") (pintype "input"))
      (node (ref "IC7") (pin "4") (pinfunction "04_~{LA}_4") (pintype "input"))
      (node (ref "PIC1") (pin "21") (pinfunction "21_PGED2/RPB10/CTED11/PMD2/RB10_21") (pintype "bidirectional"))
    )
    (net (code "45") (name "Net-(IC1-13_~{OE})") (class "Default")
      (node (ref "IC1") (pin "13") (pinfunction "13_~{OE}_13") (pintype "input"))
      (node (ref "IC2") (pin "13") (pinfunction "13_~{OE}_13") (pintype "input"))
      (node (ref "IC3") (pin "13") (pinfunction "13_~{OE}_13") (pintype "input"))
      (node (ref "IC4") (pin "13") (pinfunction "13_~{OE}_13") (pintype "input"))
      (node (ref "IC5") (pin "13") (pinfunction "13_~{OE}_13") (pintype "input"))
      (node (ref "IC6") (pin "13") (pinfunction "13_~{OE}_13") (pintype "input"))
      (node (ref "IC7") (pin "13") (pinfunction "13_~{OE}_13") (pintype "input"))
      (node (ref "PIC1") (pin "23") (pinfunction "23_AN12/PMD0/RB12_23") (pintype "bidirectional"))
    )
    (net (code "46") (name "Net-(IC1-14_SDO)") (class "Default")
      (node (ref "IC1") (pin "14") (pinfunction "14_SDO_14") (pintype "output"))
      (node (ref "IC5") (pin "2") (pinfunction "02_SDI_2") (pintype "input"))
      (node (ref "SJ3") (pin "3") (pinfunction "1_3") (pintype "passive"))
    )
    (net (code "47") (name "Net-(IC1-15_REXT)") (class "Default")
      (node (ref "IC1") (pin "15") (pinfunction "15_REXT_15") (pintype "bidirectional"))
      (node (ref "R10") (pin "1") (pinfunction "A_1") (pintype "passive"))
    )
    (net (code "48") (name "Net-(IC2-02_SDI)") (class "Default")
      (node (ref "IC2") (pin "2") (pinfunction "02_SDI_2") (pintype "input"))
      (node (ref "PIC1") (pin "22") (pinfunction "22_PGEC2/TMS/RPB11/PMD1/RB11_22") (pintype "bidirectional"))
    )
    (net (code "49") (name "Net-(IC2-15_REXT)") (class "Default")
      (node (ref "IC2") (pin "15") (pinfunction "15_REXT_15") (pintype "bidirectional"))
      (node (ref "R18") (pin "1") (pinfunction "A_1") (pintype "passive"))
    )
    (net (code "50") (name "Net-(IC3-02_SDI)") (class "Default")
      (node (ref "IC3") (pin "2") (pinfunction "02_SDI_2") (pintype "input"))
      (node (ref "IC7") (pin "14") (pinfunction "14_SDO_14") (pintype "output"))
      (node (ref "SJ1") (pin "3") (pinfunction "1_3") (pintype "passive"))
      (node (ref "SJ5") (pin "2") (pinfunction "2_2") (pintype "passive"))
    )
    (net (code "51") (name "Net-(IC3-06_OUT1)") (class "Default")
      (node (ref "IC3") (pin "6") (pinfunction "06_OUT1_6") (pintype "output"))
      (node (ref "SW1") (pin "Z-") (pinfunction "Z_Z-") (pintype "bidirectional"))
    )
    (net (code "52") (name "Net-(IC3-07_OUT2)") (class "Default")
      (node (ref "IC3") (pin "7") (pinfunction "07_OUT2_7") (pintype "output"))
      (node (ref "SW1") (pin "P-") (pinfunction "P_P-") (pintype "bidirectional"))
    )
    (net (code "53") (name "Net-(IC3-08_OUT3)") (class "Default")
      (node (ref "IC3") (pin "8") (pinfunction "08_OUT3_8") (pintype "output"))
      (node (ref "SW1") (pin "G2") (pinfunction "G2_G2") (pintype "bidirectional"))
    )
    (net (code "54") (name "Net-(IC3-10_OUT5)") (class "Default")
      (node (ref "IC3") (pin "10") (pinfunction "10_OUT5_10") (pintype "output"))
      (node (ref "SW2") (pin "Z-") (pinfunction "Z_Z-") (pintype "bidirectional"))
    )
    (net (code "55") (name "Net-(IC3-11_OUT6)") (class "Default")
      (node (ref "IC3") (pin "11") (pinfunction "11_OUT6_11") (pintype "output"))
      (node (ref "SW2") (pin "P-") (pinfunction "P_P-") (pintype "bidirectional"))
    )
    (net (code "56") (name "Net-(IC3-12_OUT7)") (class "Default")
      (node (ref "IC3") (pin "12") (pinfunction "12_OUT7_12") (pintype "output"))
      (node (ref "SW2") (pin "G2") (pinfunction "G2_G2") (pintype "bidirectional"))
    )
    (net (code "57") (name "Net-(IC3-14_SDO)") (class "Default")
      (node (ref "IC3") (pin "14") (pinfunction "14_SDO_14") (pintype "output"))
      (node (ref "IC4") (pin "2") (pinfunction "02_SDI_2") (pintype "input"))
      (node (ref "SJ1") (pin "2") (pinfunction "2_2") (pintype "passive"))
      (node (ref "SJ2") (pin "3") (pinfunction "1_3") (pintype "passive"))
    )
    (net (code "58") (name "Net-(IC3-15_REXT)") (class "Default")
      (node (ref "IC3") (pin "15") (pinfunction "15_REXT_15") (pintype "bidirectional"))
      (node (ref "R19") (pin "1") (pinfunction "A_1") (pintype "passive"))
    )
    (net (code "59") (name "Net-(IC4-06_OUT1)") (class "Default")
      (node (ref "IC4") (pin "6") (pinfunction "06_OUT1_6") (pintype "output"))
      (node (ref "SW3") (pin "Z-") (pinfunction "Z_Z-") (pintype "bidirectional"))
    )
    (net (code "60") (name "Net-(IC4-07_OUT2)") (class "Default")
      (node (ref "IC4") (pin "7") (pinfunction "07_OUT2_7") (pintype "output"))
      (node (ref "SW3") (pin "P-") (pinfunction "P_P-") (pintype "bidirectional"))
    )
    (net (code "61") (name "Net-(IC4-08_OUT3)") (class "Default")
      (node (ref "IC4") (pin "8") (pinfunction "08_OUT3_8") (pintype "output"))
      (node (ref "SW3") (pin "G2") (pinfunction "G2_G2") (pintype "bidirectional"))
    )
    (net (code "62") (name "Net-(IC4-10_OUT5)") (class "Default")
      (node (ref "IC4") (pin "10") (pinfunction "10_OUT5_10") (pintype "output"))
      (node (ref "SW4") (pin "Z-") (pinfunction "Z_Z-") (pintype "bidirectional"))
    )
    (net (code "63") (name "Net-(IC4-11_OUT6)") (class "Default")
      (node (ref "IC4") (pin "11") (pinfunction "11_OUT6_11") (pintype "output"))
      (node (ref "SW4") (pin "P-") (pinfunction "P_P-") (pintype "bidirectional"))
    )
    (net (code "64") (name "Net-(IC4-12_OUT7)") (class "Default")
      (node (ref "IC4") (pin "12") (pinfunction "12_OUT7_12") (pintype "output"))
      (node (ref "SW4") (pin "G2") (pinfunction "G2_G2") (pintype "bidirectional"))
    )
    (net (code "65") (name "Net-(IC4-14_SDO)") (class "Default")
      (node (ref "IC4") (pin "14") (pinfunction "14_SDO_14") (pintype "output"))
      (node (ref "R79") (pin "2") (pinfunction "E_2") (pintype "passive"))
      (node (ref "SJ2") (pin "2") (pinfunction "2_2") (pintype "passive"))
    )
    (net (code "66") (name "Net-(IC4-15_REXT)") (class "Default")
      (node (ref "IC4") (pin "15") (pinfunction "15_REXT_15") (pintype "bidirectional"))
      (node (ref "R20") (pin "1") (pinfunction "A_1") (pintype "passive"))
    )
    (net (code "67") (name "Net-(IC5-06_OUT1)") (class "Default")
      (node (ref "IC5") (pin "6") (pinfunction "06_OUT1_6") (pintype "output"))
      (node (ref "SW5") (pin "Z-") (pinfunction "Z_Z-") (pintype "bidirectional"))
    )
    (net (code "68") (name "Net-(IC5-07_OUT2)") (class "Default")
      (node (ref "IC5") (pin "7") (pinfunction "07_OUT2_7") (pintype "output"))
      (node (ref "SW5") (pin "P-") (pinfunction "P_P-") (pintype "bidirectional"))
    )
    (net (code "69") (name "Net-(IC5-08_OUT3)") (class "Default")
      (node (ref "IC5") (pin "8") (pinfunction "08_OUT3_8") (pintype "output"))
      (node (ref "SW5") (pin "G2") (pinfunction "G2_G2") (pintype "bidirectional"))
    )
    (net (code "70") (name "Net-(IC5-10_OUT5)") (class "Default")
      (node (ref "IC5") (pin "10") (pinfunction "10_OUT5_10") (pintype "output"))
      (node (ref "SW6") (pin "Z-") (pinfunction "Z_Z-") (pintype "bidirectional"))
    )
    (net (code "71") (name "Net-(IC5-11_OUT6)") (class "Default")
      (node (ref "IC5") (pin "11") (pinfunction "11_OUT6_11") (pintype "output"))
      (node (ref "SW6") (pin "P-") (pinfunction "P_P-") (pintype "bidirectional"))
    )
    (net (code "72") (name "Net-(IC5-12_OUT7)") (class "Default")
      (node (ref "IC5") (pin "12") (pinfunction "12_OUT7_12") (pintype "output"))
      (node (ref "SW6") (pin "G2") (pinfunction "G2_G2") (pintype "bidirectional"))
    )
    (net (code "73") (name "Net-(IC5-14_SDO)") (class "Default")
      (node (ref "IC5") (pin "14") (pinfunction "14_SDO_14") (pintype "output"))
      (node (ref "IC6") (pin "2") (pinfunction "02_SDI_2") (pintype "input"))
      (node (ref "SJ3") (pin "2") (pinfunction "2_2") (pintype "passive"))
      (node (ref "SJ4") (pin "3") (pinfunction "1_3") (pintype "passive"))
    )
    (net (code "74") (name "Net-(IC5-15_REXT)") (class "Default")
      (node (ref "IC5") (pin "15") (pinfunction "15_REXT_15") (pintype "bidirectional"))
      (node (ref "R21") (pin "1") (pinfunction "A_1") (pintype "passive"))
    )
    (net (code "75") (name "Net-(IC6-06_OUT1)") (class "Default")
      (node (ref "IC6") (pin "6") (pinfunction "06_OUT1_6") (pintype "output"))
      (node (ref "SW7") (pin "Z-") (pinfunction "Z_Z-") (pintype "bidirectional"))
    )
    (net (code "76") (name "Net-(IC6-07_OUT2)") (class "Default")
      (node (ref "IC6") (pin "7") (pinfunction "07_OUT2_7") (pintype "output"))
      (node (ref "SW7") (pin "P-") (pinfunction "P_P-") (pintype "bidirectional"))
    )
    (net (code "77") (name "Net-(IC6-08_OUT3)") (class "Default")
      (node (ref "IC6") (pin "8") (pinfunction "08_OUT3_8") (pintype "output"))
      (node (ref "SW7") (pin "G2") (pinfunction "G2_G2") (pintype "bidirectional"))
    )
    (net (code "78") (name "Net-(IC6-10_OUT5)") (class "Default")
      (node (ref "IC6") (pin "10") (pinfunction "10_OUT5_10") (pintype "output"))
      (node (ref "SW8") (pin "Z-") (pinfunction "Z_Z-") (pintype "bidirectional"))
    )
    (net (code "79") (name "Net-(IC6-11_OUT6)") (class "Default")
      (node (ref "IC6") (pin "11") (pinfunction "11_OUT6_11") (pintype "output"))
      (node (ref "SW8") (pin "P-") (pinfunction "P_P-") (pintype "bidirectional"))
    )
    (net (code "80") (name "Net-(IC6-12_OUT7)") (class "Default")
      (node (ref "IC6") (pin "12") (pinfunction "12_OUT7_12") (pintype "output"))
      (node (ref "SW8") (pin "G2") (pinfunction "G2_G2") (pintype "bidirectional"))
    )
    (net (code "81") (name "Net-(IC6-14_SDO)") (class "Default")
      (node (ref "IC6") (pin "14") (pinfunction "14_SDO_14") (pintype "output"))
      (node (ref "IC7") (pin "2") (pinfunction "02_SDI_2") (pintype "input"))
      (node (ref "SJ4") (pin "2") (pinfunction "2_2") (pintype "passive"))
      (node (ref "SJ5") (pin "3") (pinfunction "1_3") (pintype "passive"))
    )
    (net (code "82") (name "Net-(IC6-15_REXT)") (class "Default")
      (node (ref "IC6") (pin "15") (pinfunction "15_REXT_15") (pintype "bidirectional"))
      (node (ref "R22") (pin "1") (pinfunction "A_1") (pintype "passive"))
    )
    (net (code "83") (name "Net-(IC7-06_OUT1)") (class "Default")
      (node (ref "IC7") (pin "6") (pinfunction "06_OUT1_6") (pintype "output"))
      (node (ref "SW9") (pin "Z-") (pinfunction "Z_Z-") (pintype "bidirectional"))
    )
    (net (code "84") (name "Net-(IC7-07_OUT2)") (class "Default")
      (node (ref "IC7") (pin "7") (pinfunction "07_OUT2_7") (pintype "output"))
      (node (ref "SW9") (pin "P-") (pinfunction "P_P-") (pintype "bidirectional"))
    )
    (net (code "85") (name "Net-(IC7-08_OUT3)") (class "Default")
      (node (ref "IC7") (pin "8") (pinfunction "08_OUT3_8") (pintype "output"))
      (node (ref "SW9") (pin "G2") (pinfunction "G2_G2") (pintype "bidirectional"))
    )
    (net (code "86") (name "Net-(IC7-10_OUT5)") (class "Default")
      (node (ref "IC7") (pin "10") (pinfunction "10_OUT5_10") (pintype "output"))
      (node (ref "SW10") (pin "Z-") (pinfunction "Z_Z-") (pintype "bidirectional"))
    )
    (net (code "87") (name "Net-(IC7-11_OUT6)") (class "Default")
      (node (ref "IC7") (pin "11") (pinfunction "11_OUT6_11") (pintype "output"))
      (node (ref "SW10") (pin "P-") (pinfunction "P_P-") (pintype "bidirectional"))
    )
    (net (code "88") (name "Net-(IC7-12_OUT7)") (class "Default")
      (node (ref "IC7") (pin "12") (pinfunction "12_OUT7_12") (pintype "output"))
      (node (ref "SW10") (pin "G2") (pinfunction "G2_G2") (pintype "bidirectional"))
    )
    (net (code "89") (name "Net-(IC7-15_REXT)") (class "Default")
      (node (ref "IC7") (pin "15") (pinfunction "15_REXT_15") (pintype "bidirectional"))
      (node (ref "R13") (pin "1") (pinfunction "A_1") (pintype "passive"))
    )
    (net (code "90") (name "Net-(PIC1-01_~{MCLR})") (class "Default")
      (node (ref "PIC1") (pin "1") (pinfunction "01_~{MCLR}_1") (pintype "input"))
      (node (ref "PROG") (pin "3") (pinfunction "3_3") (pintype "passive"))
      (node (ref "R9") (pin "1") (pinfunction "A_1") (pintype "passive"))
    )
    (net (code "91") (name "Net-(PIC1-06_AN4{slash}C1INB{slash}C2IND{slash}RPB2{slash}SDA2{slash}CTED13{slash}RB2)") (class "Default")
      (node (ref "PIC1") (pin "6") (pinfunction "06_AN4/C1INB/C2IND/RPB2/SDA2/CTED13/RB2_6") (pintype "bidirectional"))
      (node (ref "R17") (pin "1") (pinfunction "A_1") (pintype "passive"))
      (node (ref "R79") (pin "1") (pinfunction "A_1") (pintype "passive"))
    )
    (net (code "92") (name "Net-(PIC1-09_OSC1{slash}CLKI{slash}RPA2{slash}RA2)") (class "Default")
      (node (ref "C1") (pin "1") (pinfunction "1_1") (pintype "passive"))
      (node (ref "PIC1") (pin "9") (pinfunction "09_OSC1/CLKI/RPA2/RA2_9") (pintype "bidirectional"))
      (node (ref "Q1") (pin "P$2") (pinfunction "2_P$2") (pintype "passive"))
    )
    (net (code "93") (name "Net-(PIC1-10_OSC2{slash}CLKO{slash}RPA3{slash}PMA0{slash}RA3)") (class "Default")
      (node (ref "C2") (pin "1") (pinfunction "1_1") (pintype "passive"))
      (node (ref "PIC1") (pin "10") (pinfunction "10_OSC2/CLKO/RPA3/PMA0/RA3_10") (pintype "bidirectional"))
      (node (ref "Q1") (pin "P$1") (pinfunction "1_P$1") (pintype "passive"))
    )
    (net (code "94") (name "Net-(PIC1-12_SOSCO{slash}RPA4{slash}T1CK{slash}CTED9{slash}PMA1{slash}RA4)") (class "Default")
      (node (ref "PIC1") (pin "12") (pinfunction "12_SOSCO/RPA4/T1CK/CTED9/PMA1/RA4_12") (pintype "bidirectional"))
      (node (ref "R28") (pin "2") (pinfunction "E_2") (pintype "passive"))
      (node (ref "R31") (pin "1") (pinfunction "A_1") (pintype "passive"))
    )
    (net (code "95") (name "Net-(PIC1-14_PGED3{slash}RPB5{slash}PMD7{slash}RB5)") (class "Default")
      (node (ref "CN_SYSTEM") (pin "11") (pinfunction "11_11") (pintype "passive"))
      (node (ref "CN_SYSTEM") (pin "12") (pinfunction "12_12") (pintype "passive"))
      (node (ref "PIC1") (pin "14") (pinfunction "14_PGED3/RPB5/PMD7/RB5_14") (pintype "bidirectional"))
      (node (ref "PROG") (pin "4") (pinfunction "4_4") (pintype "passive"))
    )
    (net (code "96") (name "Net-(PIC1-15_PGEC3{slash}RPB6{slash}PMD6{slash}RB6)") (class "Default")
      (node (ref "PIC1") (pin "15") (pinfunction "15_PGEC3/RPB6/PMD6/RB6_15") (pintype "bidirectional"))
      (node (ref "PROG") (pin "5") (pinfunction "5_5") (pintype "passive"))
      (node (ref "R27") (pin "2") (pinfunction "E_2") (pintype "passive"))
      (node (ref "SW1") (pin "G1") (pinfunction "G1_G1") (pintype "bidirectional"))
      (node (ref "SW10") (pin "G1") (pinfunction "G1_G1") (pintype "bidirectional"))
      (node (ref "SW2") (pin "G1") (pinfunction "G1_G1") (pintype "bidirectional"))
      (node (ref "SW3") (pin "G1") (pinfunction "G1_G1") (pintype "bidirectional"))
      (node (ref "SW4") (pin "G1") (pinfunction "G1_G1") (pintype "bidirectional"))
      (node (ref "SW5") (pin "G1") (pinfunction "G1_G1") (pintype "bidirectional"))
      (node (ref "SW6") (pin "G1") (pinfunction "G1_G1") (pintype "bidirectional"))
      (node (ref "SW7") (pin "G1") (pinfunction "G1_G1") (pintype "bidirectional"))
      (node (ref "SW8") (pin "G1") (pinfunction "G1_G1") (pintype "bidirectional"))
      (node (ref "SW9") (pin "G1") (pinfunction "G1_G1") (pintype "bidirectional"))
    )
    (net (code "97") (name "Net-(PIC1-16_TDI{slash}RPB7{slash}CTED3{slash}PMD5{slash}INT0{slash}RB7)") (class "Default")
      (node (ref "CN_SYSTEM") (pin "13") (pinfunction "13_13") (pintype "passive"))
      (node (ref "CN_SYSTEM") (pin "14") (pinfunction "14_14") (pintype "passive"))
      (node (ref "PIC1") (pin "16") (pinfunction "16_TDI/RPB7/CTED3/PMD5/INT0/RB7_16") (pintype "bidirectional"))
    )
    (net (code "98") (name "Net-(PIC1-17_TCK{slash}RPB8{slash}SCL1{slash}CTED10{slash}PMD4{slash}RB8)") (class "Default")
      (node (ref "PIC1") (pin "17") (pinfunction "17_TCK/RPB8/SCL1/CTED10/PMD4/RB8_17") (pintype "bidirectional"))
      (node (ref "R29") (pin "1") (pinfunction "A_1") (pintype "passive"))
    )
    (net (code "99") (name "Net-(PIC1-18_TDO{slash}RPB9{slash}SDA1{slash}CTED4{slash}PMD3{slash}RB9)") (class "Default")
      (node (ref "PIC1") (pin "18") (pinfunction "18_TDO/RPB9/SDA1/CTED4/PMD3/RB9_18") (pintype "bidirectional"))
      (node (ref "R30") (pin "1") (pinfunction "A_1") (pintype "passive"))
    )
    (net (code "100") (name "Net-(PIC1-20_VCAP)") (class "Default")
      (node (ref "C6") (pin "1") (pinfunction "1_1") (pintype "passive"))
      (node (ref "PIC1") (pin "20") (pinfunction "20_VCAP_20") (pintype "power_in"))
    )
    (net (code "101") (name "Net-(PIC1-24_AN11{slash}RPB13{slash}CTPLS{slash}PMRD{slash}RB13)") (class "Default")
      (node (ref "CN_SYSTEM") (pin "10") (pinfunction "10_10") (pintype "passive"))
      (node (ref "CN_SYSTEM") (pin "9") (pinfunction "9_9") (pintype "passive"))
      (node (ref "PIC1") (pin "24") (pinfunction "24_AN11/RPB13/CTPLS/PMRD/RB13_24") (pintype "bidirectional"))
    )
    (net (code "102") (name "Net-(PIC1-25_CVREFOUT{slash}AN10{slash}C3INB{slash}RPB14{slash}SCK1{slash}CTED5{slash}PMWR{slash}RB14)") (class "Default")
      (node (ref "CN_SYSTEM") (pin "7") (pinfunction "7_7") (pintype "passive"))
      (node (ref "CN_SYSTEM") (pin "8") (pinfunction "8_8") (pintype "passive"))
      (node (ref "PIC1") (pin "25") (pinfunction "25_CVREFOUT/AN10/C3INB/RPB14/SCK1/CTED5/PMWR/RB14_25") (pintype "bidirectional"))
      (node (ref "R14") (pin "1") (pinfunction "A_1") (pintype "passive"))
    )
    (net (code "103") (name "Net-(Q2-B)") (class "Default")
      (node (ref "Q2") (pin "1") (pinfunction "B_1") (pintype "passive"))
      (node (ref "R17") (pin "2") (pinfunction "E_2") (pintype "passive"))
    )
    (net (code "104") (name "Net-(Q2-C)") (class "Default")
      (node (ref "Q2") (pin "3") (pinfunction "C_3") (pintype "passive"))
      (node (ref "R26") (pin "2") (pinfunction "E_2") (pintype "passive"))
    )
    (net (code "105") (name "Net-(R1-E)") (class "Default")
      (node (ref "R1") (pin "2") (pinfunction "E_2") (pintype "passive"))
      (node (ref "R11") (pin "2") (pinfunction "E_2") (pintype "passive"))
      (node (ref "R12") (pin "1") (pinfunction "A_1") (pintype "passive"))
      (node (ref "R2") (pin "1") (pinfunction "A_1") (pintype "passive"))
      (node (ref "R26") (pin "1") (pinfunction "A_1") (pintype "passive"))
      (node (ref "R3") (pin "2") (pinfunction "E_2") (pintype "passive"))
      (node (ref "R4") (pin "1") (pinfunction "A_1") (pintype "passive"))
      (node (ref "R5") (pin "2") (pinfunction "E_2") (pintype "passive"))
      (node (ref "R6") (pin "1") (pinfunction "A_1") (pintype "passive"))
      (node (ref "R7") (pin "2") (pinfunction "E_2") (pintype "passive"))
      (node (ref "R8") (pin "1") (pinfunction "A_1") (pintype "passive"))
    )
    (net (code "106") (name "Net-(R10-E)") (class "Default")
      (node (ref "C20") (pin "P+") (pinfunction "P+_P+") (pintype "passive"))
      (node (ref "R10") (pin "2") (pinfunction "E_2") (pintype "passive"))
      (node (ref "R13") (pin "2") (pinfunction "E_2") (pintype "passive"))
      (node (ref "R18") (pin "2") (pinfunction "E_2") (pintype "passive"))
      (node (ref "R19") (pin "2") (pinfunction "E_2") (pintype "passive"))
      (node (ref "R20") (pin "2") (pinfunction "E_2") (pintype "passive"))
      (node (ref "R21") (pin "2") (pinfunction "E_2") (pintype "passive"))
      (node (ref "R22") (pin "2") (pinfunction "E_2") (pintype "passive"))
      (node (ref "R31") (pin "2") (pinfunction "E_2") (pintype "passive"))
      (node (ref "R32") (pin "1") (pinfunction "A_1") (pintype "passive"))
    )
    (net (code "107") (name "Net-(R51-A)") (class "Default")
      (node (ref "C28") (pin "2") (pinfunction "2_2") (pintype "passive"))
      (node (ref "R51") (pin "1") (pinfunction "A_1") (pintype "passive"))
    )
    (net (code "108") (name "unconnected-(IC1-11_OUT6-Pad11)") (class "Default")
      (node (ref "IC1") (pin "11") (pinfunction "11_OUT6_11") (pintype "output"))
    )
    (net (code "109") (name "unconnected-(IC1-12_OUT7-Pad12)") (class "Default")
      (node (ref "IC1") (pin "12") (pinfunction "12_OUT7_12") (pintype "output"))
    )
    (net (code "110") (name "unconnected-(IC2-11_OUT6-Pad11)") (class "Default")
      (node (ref "IC2") (pin "11") (pinfunction "11_OUT6_11") (pintype "output"))
    )
    (net (code "111") (name "unconnected-(IC2-12_OUT7-Pad12)") (class "Default")
      (node (ref "IC2") (pin "12") (pinfunction "12_OUT7_12") (pintype "output"))
    )
    (net (code "112") (name "unconnected-(PIC1-02_VREF+{slash}VREF+{slash}AN0{slash}C3INC{slash}RPA0{slash}CTED1{slash}RA0-Pad2)") (class "Default")
      (node (ref "PIC1") (pin "2") (pinfunction "02_VREF+/VREF+/AN0/C3INC/RPA0/CTED1/RA0_2") (pintype "bidirectional"))
    )
    (net (code "113") (name "unconnected-(PIC1-03_VREF-{slash}CVREF-{slash}AN1{slash}RPA1{slash}CTED2{slash}RA1-Pad3)") (class "Default")
      (node (ref "PIC1") (pin "3") (pinfunction "03_VREF-/CVREF-/AN1/RPA1/CTED2/RA1_3") (pintype "bidirectional"))
    )
    (net (code "114") (name "unconnected-(PIC1-04_PGED1{slash}AN2{slash}C1IND{slash}C2INB{slash}C3IND{slash}RPB0{slash}RB0-Pad4)") (class "Default")
      (node (ref "PIC1") (pin "4") (pinfunction "04_PGED1/AN2/C1IND/C2INB/C3IND/RPB0/RB0_4") (pintype "bidirectional"))
    )
    (net (code "115") (name "unconnected-(PIC1-05_PGEC1{slash}AN3{slash}C1INC{slash}C2INA{slash}RPB1{slash}CTED12{slash}RB1-Pad5)") (class "Default")
      (node (ref "PIC1") (pin "5") (pinfunction "05_PGEC1/AN3/C1INC/C2INA/RPB1/CTED12/RB1_5") (pintype "bidirectional"))
    )
    (net (code "116") (name "unconnected-(PIC1-07_AN5{slash}C1INA{slash}C2INC{slash}RTCC{slash}RPB3{slash}SCL2{slash}RB3-Pad7)") (class "Default")
      (node (ref "PIC1") (pin "7") (pinfunction "07_AN5/C1INA/C2INC/RTCC/RPB3/SCL2/RB3_7") (pintype "bidirectional"))
    )
    (net (code "117") (name "unconnected-(PIC1-11_SOSCI{slash}RPB4{slash}RB4-Pad11)") (class "Default")
      (node (ref "PIC1") (pin "11") (pinfunction "11_SOSCI/RPB4/RB4_11") (pintype "bidirectional"))
    )
  )
)
